# Schematic.net
KiCad netlist of a schematic drawn in EasyEDA
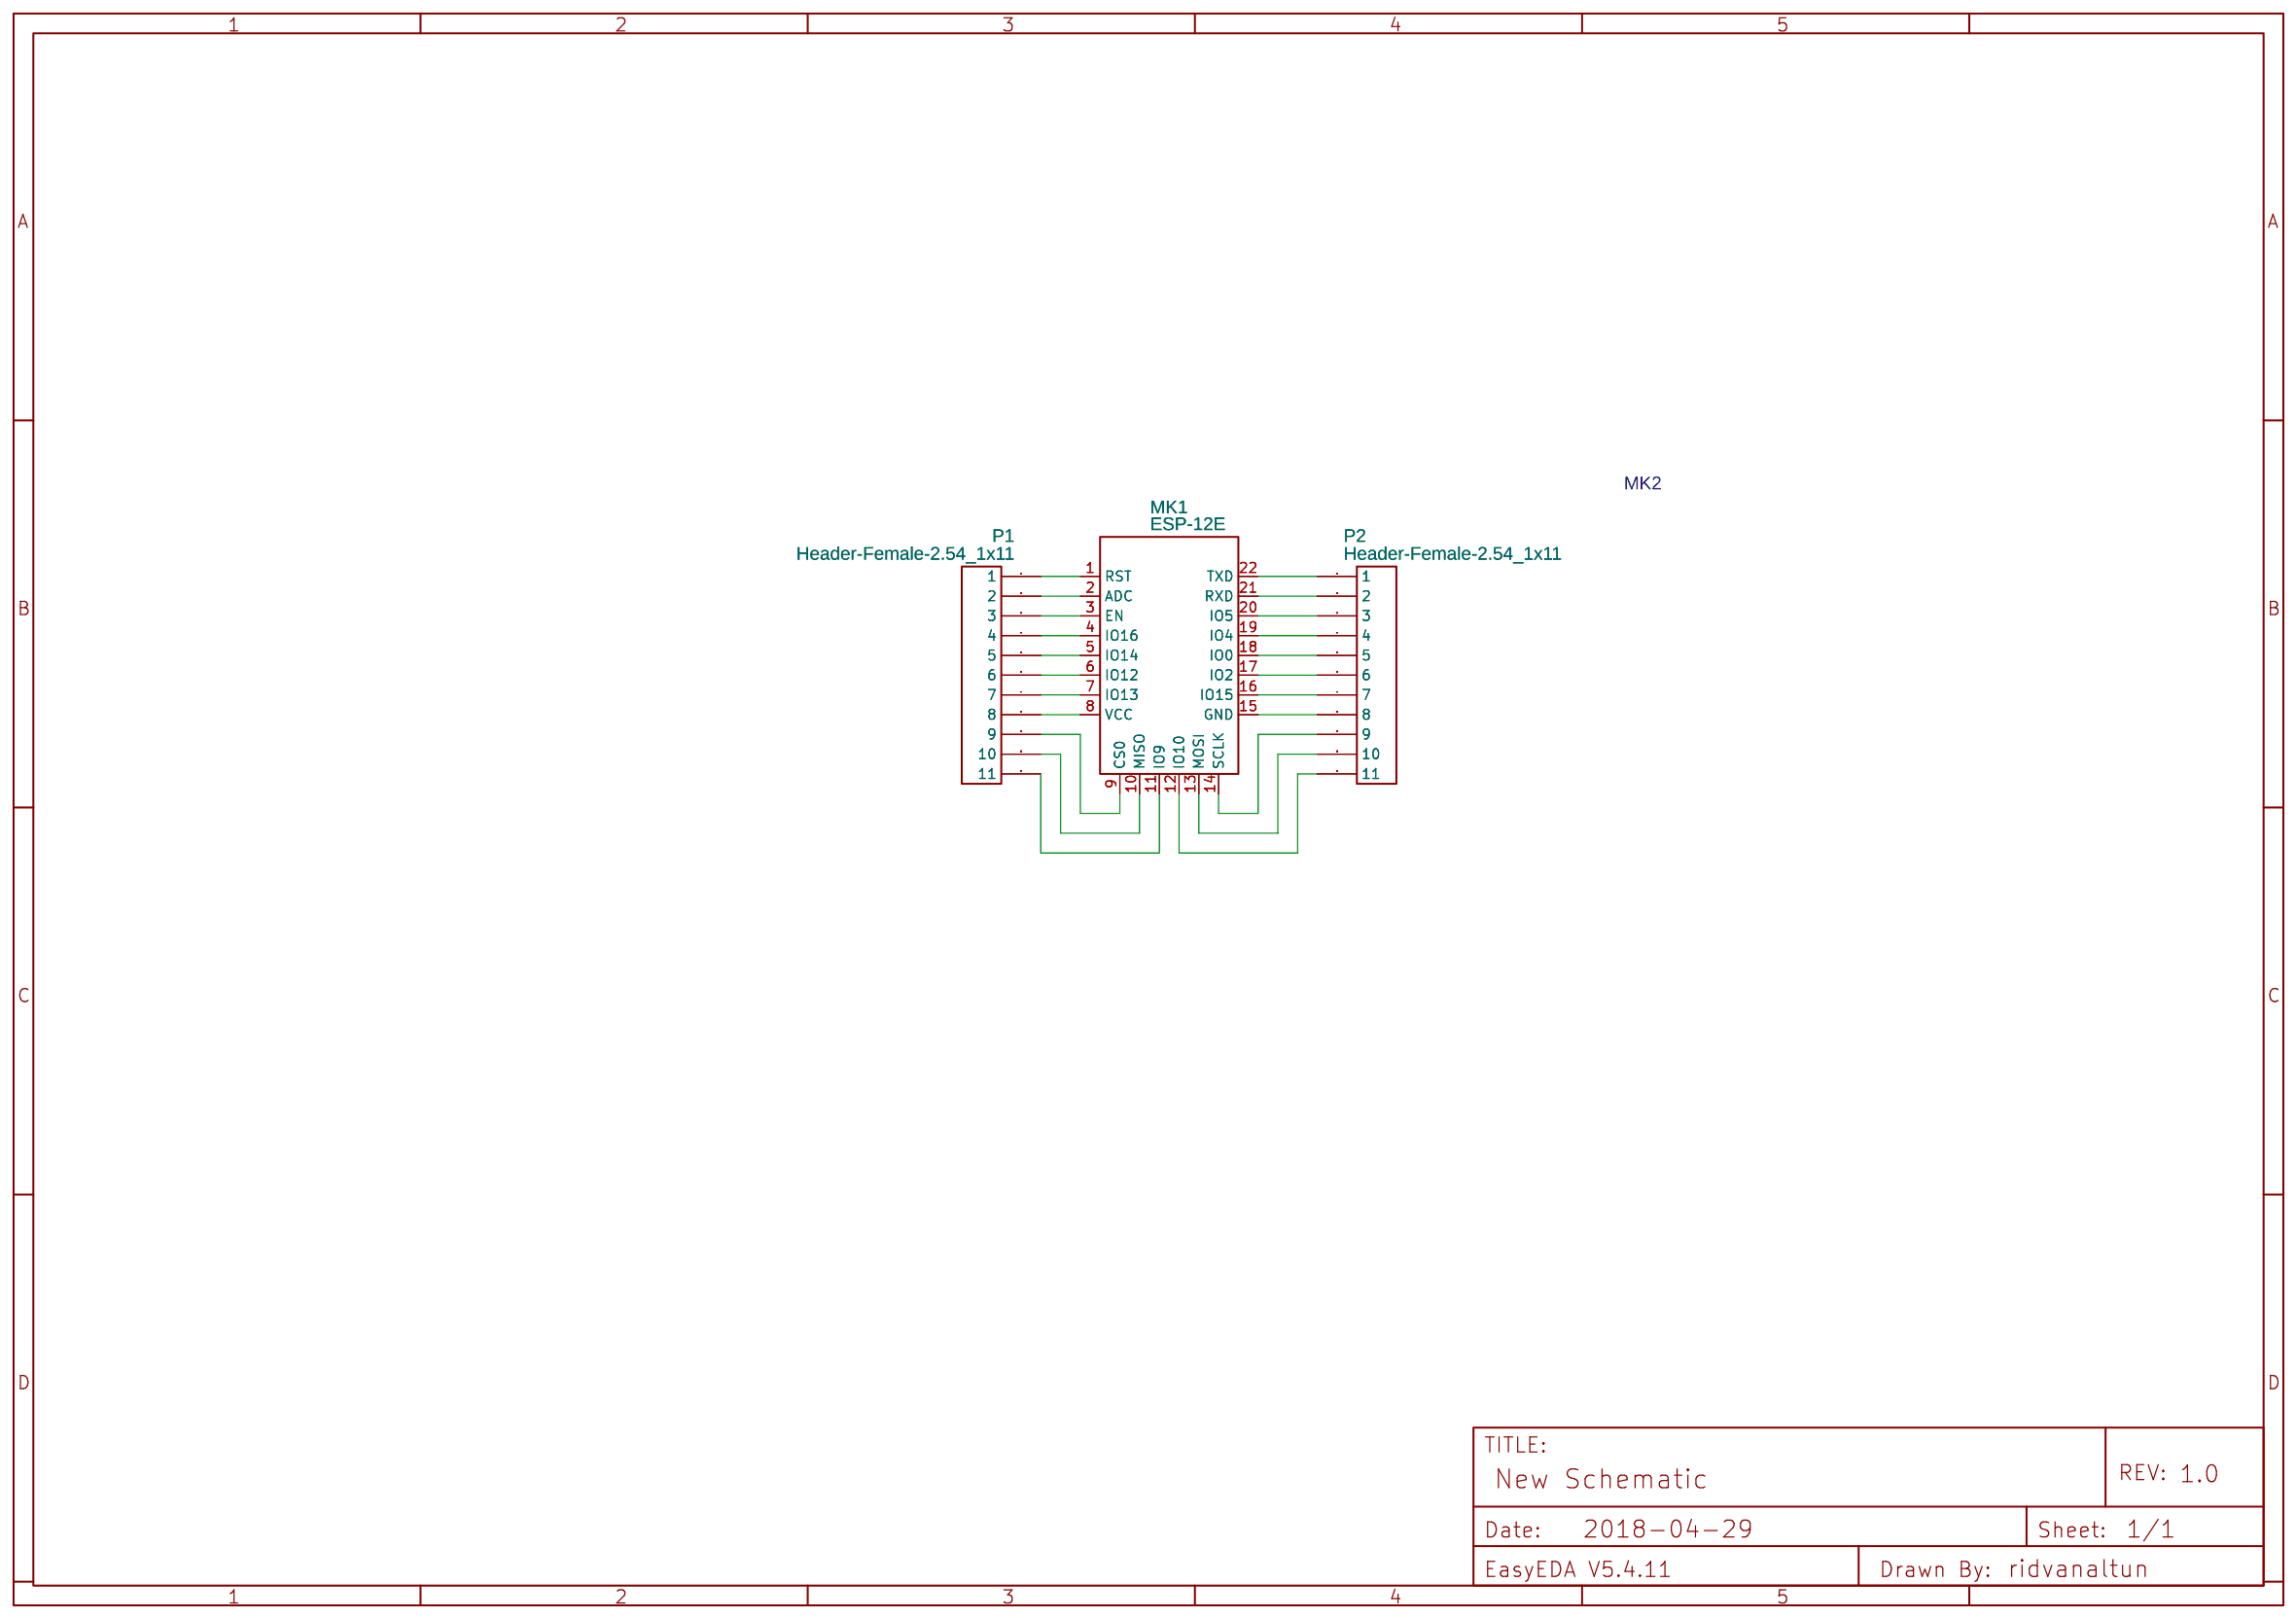
[diagram p0: schematic sheet]

(export (version "E")
  (design (tool "Eeschema 10.0.6"))
  (components
    (comp (ref "MK1") (value "ESP-12E") (libsource (lib "") (part "Unknown_590_315")))
    (comp (ref "P1")
      (value "Header-Female-2.54_1x11")
      (fields (field (name "BOM_Manufacturer Part") "Header-Female-2.54_1x10"))
      (libsource (lib "") (part "Unknown_505_335"))
    )
    (comp (ref "P2")
      (value "Header-Female-2.54_1x11")
      (fields (field (name "BOM_Manufacturer Part") "Header-Female-2.54_1x10"))
      (libsource (lib "") (part "Unknown_675_335"))
    )
  )
  (nets
    (net (code "1") (name "Net-(MK1-ADC)") (class "Default")
      (node (ref "MK1") (pin "2") (pinfunction "ADC_2") (pintype "unspecified"))
      (node (ref "P1") (pin "2") (pinfunction "2_2") (pintype "input"))
    )
    (net (code "2") (name "Net-(MK1-CS0)") (class "Default")
      (node (ref "MK1") (pin "9") (pinfunction "CS0_9") (pintype "unspecified"))
      (node (ref "P1") (pin "9") (pinfunction "9_9") (pintype "input"))
    )
    (net (code "3") (name "Net-(MK1-EN)") (class "Default")
      (node (ref "MK1") (pin "3") (pinfunction "EN_3") (pintype "unspecified"))
      (node (ref "P1") (pin "3") (pinfunction "3_3") (pintype "input"))
    )
    (net (code "4") (name "Net-(MK1-GND)") (class "Default")
      (node (ref "MK1") (pin "15") (pinfunction "GND_15") (pintype "unspecified"))
      (node (ref "P2") (pin "8") (pinfunction "8_8") (pintype "input"))
    )
    (net (code "5") (name "Net-(MK1-IO0)") (class "Default")
      (node (ref "MK1") (pin "18") (pinfunction "IO0_18") (pintype "unspecified"))
      (node (ref "P2") (pin "5") (pinfunction "5_5") (pintype "input"))
    )
    (net (code "6") (name "Net-(MK1-IO2)") (class "Default")
      (node (ref "MK1") (pin "17") (pinfunction "IO2_17") (pintype "unspecified"))
      (node (ref "P2") (pin "6") (pinfunction "6_6") (pintype "input"))
    )
    (net (code "7") (name "Net-(MK1-IO4)") (class "Default")
      (node (ref "MK1") (pin "19") (pinfunction "IO4_19") (pintype "unspecified"))
      (node (ref "P2") (pin "4") (pinfunction "4_4") (pintype "input"))
    )
    (net (code "8") (name "Net-(MK1-IO5)") (class "Default")
      (node (ref "MK1") (pin "20") (pinfunction "IO5_20") (pintype "unspecified"))
      (node (ref "P2") (pin "3") (pinfunction "3_3") (pintype "input"))
    )
    (net (code "9") (name "Net-(MK1-IO9)") (class "Default")
      (node (ref "MK1") (pin "11") (pinfunction "IO9_11") (pintype "unspecified"))
      (node (ref "P1") (pin "11") (pinfunction "11_11") (pintype "input"))
    )
    (net (code "10") (name "Net-(MK1-IO10)") (class "Default")
      (node (ref "MK1") (pin "12") (pinfunction "IO10_12") (pintype "unspecified"))
      (node (ref "P2") (pin "11") (pinfunction "11_11") (pintype "input"))
    )
    (net (code "11") (name "Net-(MK1-IO12)") (class "Default")
      (node (ref "MK1") (pin "6") (pinfunction "IO12_6") (pintype "unspecified"))
      (node (ref "P1") (pin "6") (pinfunction "6_6") (pintype "input"))
    )
    (net (code "12") (name "Net-(MK1-IO13)") (class "Default")
      (node (ref "MK1") (pin "7") (pinfunction "IO13_7") (pintype "unspecified"))
      (node (ref "P1") (pin "7") (pinfunction "7_7") (pintype "input"))
    )
    (net (code "13") (name "Net-(MK1-IO14)") (class "Default")
      (node (ref "MK1") (pin "5") (pinfunction "IO14_5") (pintype "unspecified"))
      (node (ref "P1") (pin "5") (pinfunction "5_5") (pintype "input"))
    )
    (net (code "14") (name "Net-(MK1-IO15)") (class "Default")
      (node (ref "MK1") (pin "16") (pinfunction "IO15_16") (pintype "unspecified"))
      (node (ref "P2") (pin "7") (pinfunction "7_7") (pintype "input"))
    )
    (net (code "15") (name "Net-(MK1-IO16)") (class "Default")
      (node (ref "MK1") (pin "4") (pinfunction "IO16_4") (pintype "unspecified"))
      (node (ref "P1") (pin "4") (pinfunction "4_4") (pintype "input"))
    )
    (net (code "16") (name "Net-(MK1-MISO)") (class "Default")
      (node (ref "MK1") (pin "10") (pinfunction "MISO_10") (pintype "unspecified"))
      (node (ref "P1") (pin "10") (pinfunction "10_10") (pintype "input"))
    )
    (net (code "17") (name "Net-(MK1-MOSI)") (class "Default")
      (node (ref "MK1") (pin "13") (pinfunction "MOSI_13") (pintype "unspecified"))
      (node (ref "P2") (pin "10") (pinfunction "10_10") (pintype "input"))
    )
    (net (code "18") (name "Net-(MK1-RST)") (class "Default")
      (node (ref "MK1") (pin "1") (pinfunction "RST_1") (pintype "unspecified"))
      (node (ref "P1") (pin "1") (pinfunction "1_1") (pintype "input"))
    )
    (net (code "19") (name "Net-(MK1-RXD)") (class "Default")
      (node (ref "MK1") (pin "21") (pinfunction "RXD_21") (pintype "unspecified"))
      (node (ref "P2") (pin "2") (pinfunction "2_2") (pintype "input"))
    )
    (net (code "20") (name "Net-(MK1-SCLK)") (class "Default")
      (node (ref "MK1") (pin "14") (pinfunction "SCLK_14") (pintype "unspecified"))
      (node (ref "P2") (pin "9") (pinfunction "9_9") (pintype "input"))
    )
    (net (code "21") (name "Net-(MK1-TXD)") (class "Default")
      (node (ref "MK1") (pin "22") (pinfunction "TXD_22") (pintype "unspecified"))
      (node (ref "P2") (pin "1") (pinfunction "1_1") (pintype "input"))
    )
    (net (code "22") (name "Net-(MK1-VCC)") (class "Default")
      (node (ref "MK1") (pin "8") (pinfunction "VCC_8") (pintype "unspecified"))
      (node (ref "P1") (pin "8") (pinfunction "8_8") (pintype "input"))
    )
  )
)
